# Simple.net
KiCad netlist of a schematic drawn in EAGLE
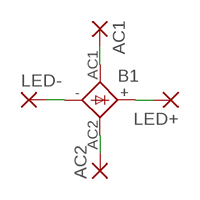
[diagram p0: schematic, sheet 1]

(export (version "E")
  (design (tool "Eeschema 10.0.6"))
  (components
    (comp (ref "AC1")
      (value "WIREPAD-SMD2")
      (footprint "eagle-import:PAD-1.27X2.54")
      (libsource (lib "eagle-import") (part "WIREPAD-SMD2"))
    )
    (comp (ref "AC2")
      (value "WIREPAD-SMD2")
      (footprint "eagle-import:PAD-1.27X2.54")
      (libsource (lib "eagle-import") (part "WIREPAD-SMD2"))
    )
    (comp (ref "B1")
      (value "BRIDGEDBS")
      (footprint "eagle-import:DBS")
      (libsource (lib "eagle-import") (part "BRIDGEDBS"))
    )
    (comp (ref "LED+")
      (value "WIREPAD-SMD2")
      (footprint "eagle-import:PAD-1.27X2.54")
      (libsource (lib "eagle-import") (part "WIREPAD-SMD2"))
    )
    (comp (ref "LED-")
      (value "WIREPAD-SMD2")
      (footprint "eagle-import:PAD-1.27X2.54")
      (libsource (lib "eagle-import") (part "WIREPAD-SMD2"))
    )
  )
  (nets
    (net (code "1") (name "Net-(AC1-P)") (class "Default")
      (node (ref "AC1") (pin "P$1") (pinfunction "P_P$1") (pintype "passive"))
      (node (ref "B1") (pin "AC1") (pinfunction "AC1_AC1") (pintype "passive"))
    )
    (net (code "2") (name "Net-(AC2-P)") (class "Default")
      (node (ref "AC2") (pin "P$1") (pinfunction "P_P$1") (pintype "passive"))
      (node (ref "B1") (pin "AC2") (pinfunction "AC2_AC2") (pintype "passive"))
    )
    (net (code "3") (name "Net-(LED+-P)") (class "Default")
      (node (ref "B1") (pin "+") (pinfunction "+_+") (pintype "passive"))
      (node (ref "LED+") (pin "P$1") (pinfunction "P_P$1") (pintype "passive"))
    )
    (net (code "4") (name "Net-(LED--P)") (class "Default")
      (node (ref "B1") (pin "-") (pinfunction "-_-") (pintype "passive"))
      (node (ref "LED-") (pin "P$1") (pinfunction "P_P$1") (pintype "passive"))
    )
  )
)
